# Pg2_Battery_Contacts.net
KiCad netlist of a schematic drawn in Altium Designer
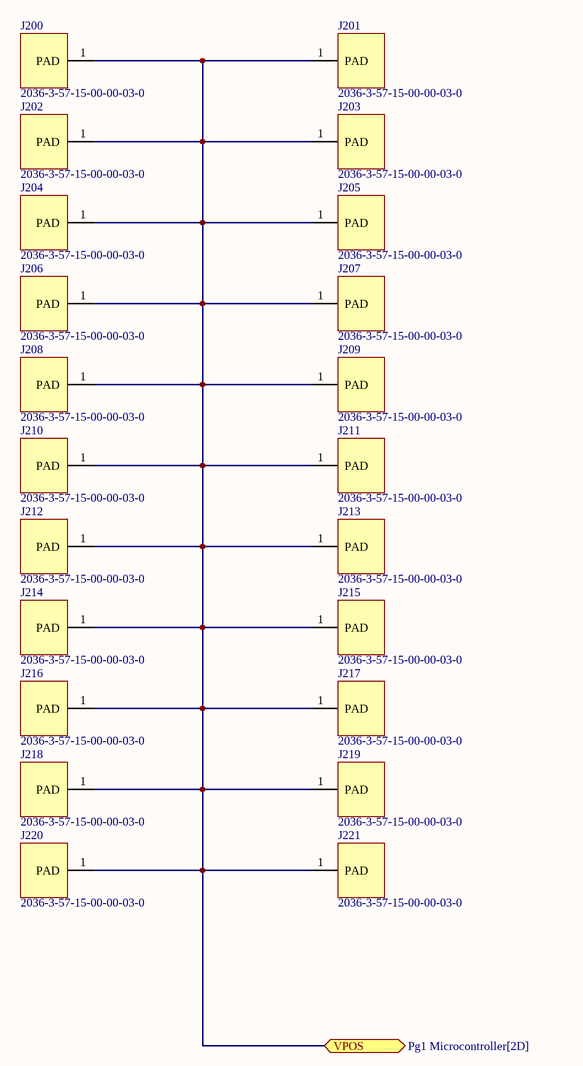
[diagram p0: Pg2_Battery_Contacts.SchDoc]

(export (version "E")
  (design (tool "Eeschema 10.0.6"))
  (components
    (comp (ref "J200")
      (value "2036-3-57-15-00-00-03-0")
      (footprint "6mm Pad")
      (description "Hardware, Sprint Contact Surface")
      (libsource (lib "") (part "2036-3-57-15-00-00-03-0_1"))
    )
    (comp (ref "J201")
      (value "2036-3-57-15-00-00-03-0")
      (footprint "6mm Pad")
      (description "Hardware, Sprint Contact Surface")
      (libsource (lib "SchLib - EE391 Master") (part "2036-3-57-15-00-00-03-0"))
    )
    (comp (ref "J202")
      (value "2036-3-57-15-00-00-03-0")
      (footprint "6mm Pad")
      (description "Hardware, Sprint Contact Surface")
      (libsource (lib "") (part "2036-3-57-15-00-00-03-0_1"))
    )
    (comp (ref "J203")
      (value "2036-3-57-15-00-00-03-0")
      (footprint "6mm Pad")
      (description "Hardware, Sprint Contact Surface")
      (libsource (lib "SchLib - EE391 Master") (part "2036-3-57-15-00-00-03-0"))
    )
    (comp (ref "J204")
      (value "2036-3-57-15-00-00-03-0")
      (footprint "6mm Pad")
      (description "Hardware, Sprint Contact Surface")
      (libsource (lib "") (part "2036-3-57-15-00-00-03-0_1"))
    )
    (comp (ref "J205")
      (value "2036-3-57-15-00-00-03-0")
      (footprint "6mm Pad")
      (description "Hardware, Sprint Contact Surface")
      (libsource (lib "SchLib - EE391 Master") (part "2036-3-57-15-00-00-03-0"))
    )
    (comp (ref "J206")
      (value "2036-3-57-15-00-00-03-0")
      (footprint "6mm Pad")
      (description "Hardware, Sprint Contact Surface")
      (libsource (lib "") (part "2036-3-57-15-00-00-03-0_1"))
    )
    (comp (ref "J207")
      (value "2036-3-57-15-00-00-03-0")
      (footprint "6mm Pad")
      (description "Hardware, Sprint Contact Surface")
      (libsource (lib "SchLib - EE391 Master") (part "2036-3-57-15-00-00-03-0"))
    )
    (comp (ref "J208")
      (value "2036-3-57-15-00-00-03-0")
      (footprint "6mm Pad")
      (description "Hardware, Sprint Contact Surface")
      (libsource (lib "") (part "2036-3-57-15-00-00-03-0_1"))
    )
    (comp (ref "J209")
      (value "2036-3-57-15-00-00-03-0")
      (footprint "6mm Pad")
      (description "Hardware, Sprint Contact Surface")
      (libsource (lib "SchLib - EE391 Master") (part "2036-3-57-15-00-00-03-0"))
    )
    (comp (ref "J210")
      (value "2036-3-57-15-00-00-03-0")
      (footprint "6mm Pad")
      (description "Hardware, Sprint Contact Surface")
      (libsource (lib "") (part "2036-3-57-15-00-00-03-0_1"))
    )
    (comp (ref "J211")
      (value "2036-3-57-15-00-00-03-0")
      (footprint "6mm Pad")
      (description "Hardware, Sprint Contact Surface")
      (libsource (lib "SchLib - EE391 Master") (part "2036-3-57-15-00-00-03-0"))
    )
    (comp (ref "J212")
      (value "2036-3-57-15-00-00-03-0")
      (footprint "6mm Pad")
      (description "Hardware, Sprint Contact Surface")
      (libsource (lib "") (part "2036-3-57-15-00-00-03-0_1"))
    )
    (comp (ref "J213")
      (value "2036-3-57-15-00-00-03-0")
      (footprint "6mm Pad")
      (description "Hardware, Sprint Contact Surface")
      (libsource (lib "SchLib - EE391 Master") (part "2036-3-57-15-00-00-03-0"))
    )
    (comp (ref "J214")
      (value "2036-3-57-15-00-00-03-0")
      (footprint "6mm Pad")
      (description "Hardware, Sprint Contact Surface")
      (libsource (lib "") (part "2036-3-57-15-00-00-03-0_1"))
    )
    (comp (ref "J215")
      (value "2036-3-57-15-00-00-03-0")
      (footprint "6mm Pad")
      (description "Hardware, Sprint Contact Surface")
      (libsource (lib "SchLib - EE391 Master") (part "2036-3-57-15-00-00-03-0"))
    )
    (comp (ref "J216")
      (value "2036-3-57-15-00-00-03-0")
      (footprint "6mm Pad")
      (description "Hardware, Sprint Contact Surface")
      (libsource (lib "") (part "2036-3-57-15-00-00-03-0_1"))
    )
    (comp (ref "J217")
      (value "2036-3-57-15-00-00-03-0")
      (footprint "6mm Pad")
      (description "Hardware, Sprint Contact Surface")
      (libsource (lib "SchLib - EE391 Master") (part "2036-3-57-15-00-00-03-0"))
    )
    (comp (ref "J218")
      (value "2036-3-57-15-00-00-03-0")
      (footprint "6mm Pad")
      (description "Hardware, Sprint Contact Surface")
      (libsource (lib "") (part "2036-3-57-15-00-00-03-0_1"))
    )
    (comp (ref "J219")
      (value "2036-3-57-15-00-00-03-0")
      (footprint "6mm Pad")
      (description "Hardware, Sprint Contact Surface")
      (libsource (lib "SchLib - EE391 Master") (part "2036-3-57-15-00-00-03-0"))
    )
    (comp (ref "J220")
      (value "2036-3-57-15-00-00-03-0")
      (footprint "6mm Pad")
      (description "Hardware, Sprint Contact Surface")
      (libsource (lib "") (part "2036-3-57-15-00-00-03-0_1"))
    )
    (comp (ref "J221")
      (value "2036-3-57-15-00-00-03-0")
      (footprint "6mm Pad")
      (description "Hardware, Sprint Contact Surface")
      (libsource (lib "SchLib - EE391 Master") (part "2036-3-57-15-00-00-03-0"))
    )
  )
  (nets
    (net (code "1") (name "/VPOS") (class "Default")
      (node (ref "J200") (pin "1") (pinfunction "PAD_1") (pintype "passive"))
      (node (ref "J201") (pin "1") (pinfunction "PAD_1") (pintype "passive"))
      (node (ref "J202") (pin "1") (pinfunction "PAD_1") (pintype "passive"))
      (node (ref "J203") (pin "1") (pinfunction "PAD_1") (pintype "passive"))
      (node (ref "J204") (pin "1") (pinfunction "PAD_1") (pintype "passive"))
      (node (ref "J205") (pin "1") (pinfunction "PAD_1") (pintype "passive"))
      (node (ref "J206") (pin "1") (pinfunction "PAD_1") (pintype "passive"))
      (node (ref "J207") (pin "1") (pinfunction "PAD_1") (pintype "passive"))
      (node (ref "J208") (pin "1") (pinfunction "PAD_1") (pintype "passive"))
      (node (ref "J209") (pin "1") (pinfunction "PAD_1") (pintype "passive"))
      (node (ref "J210") (pin "1") (pinfunction "PAD_1") (pintype "passive"))
      (node (ref "J211") (pin "1") (pinfunction "PAD_1") (pintype "passive"))
      (node (ref "J212") (pin "1") (pinfunction "PAD_1") (pintype "passive"))
      (node (ref "J213") (pin "1") (pinfunction "PAD_1") (pintype "passive"))
      (node (ref "J214") (pin "1") (pinfunction "PAD_1") (pintype "passive"))
      (node (ref "J215") (pin "1") (pinfunction "PAD_1") (pintype "passive"))
      (node (ref "J216") (pin "1") (pinfunction "PAD_1") (pintype "passive"))
      (node (ref "J217") (pin "1") (pinfunction "PAD_1") (pintype "passive"))
      (node (ref "J218") (pin "1") (pinfunction "PAD_1") (pintype "passive"))
      (node (ref "J219") (pin "1") (pinfunction "PAD_1") (pintype "passive"))
      (node (ref "J220") (pin "1") (pinfunction "PAD_1") (pintype "passive"))
      (node (ref "J221") (pin "1") (pinfunction "PAD_1") (pintype "passive"))
    )
  )
)
